# 1.net
KiCad netlist of a schematic drawn in EAGLE
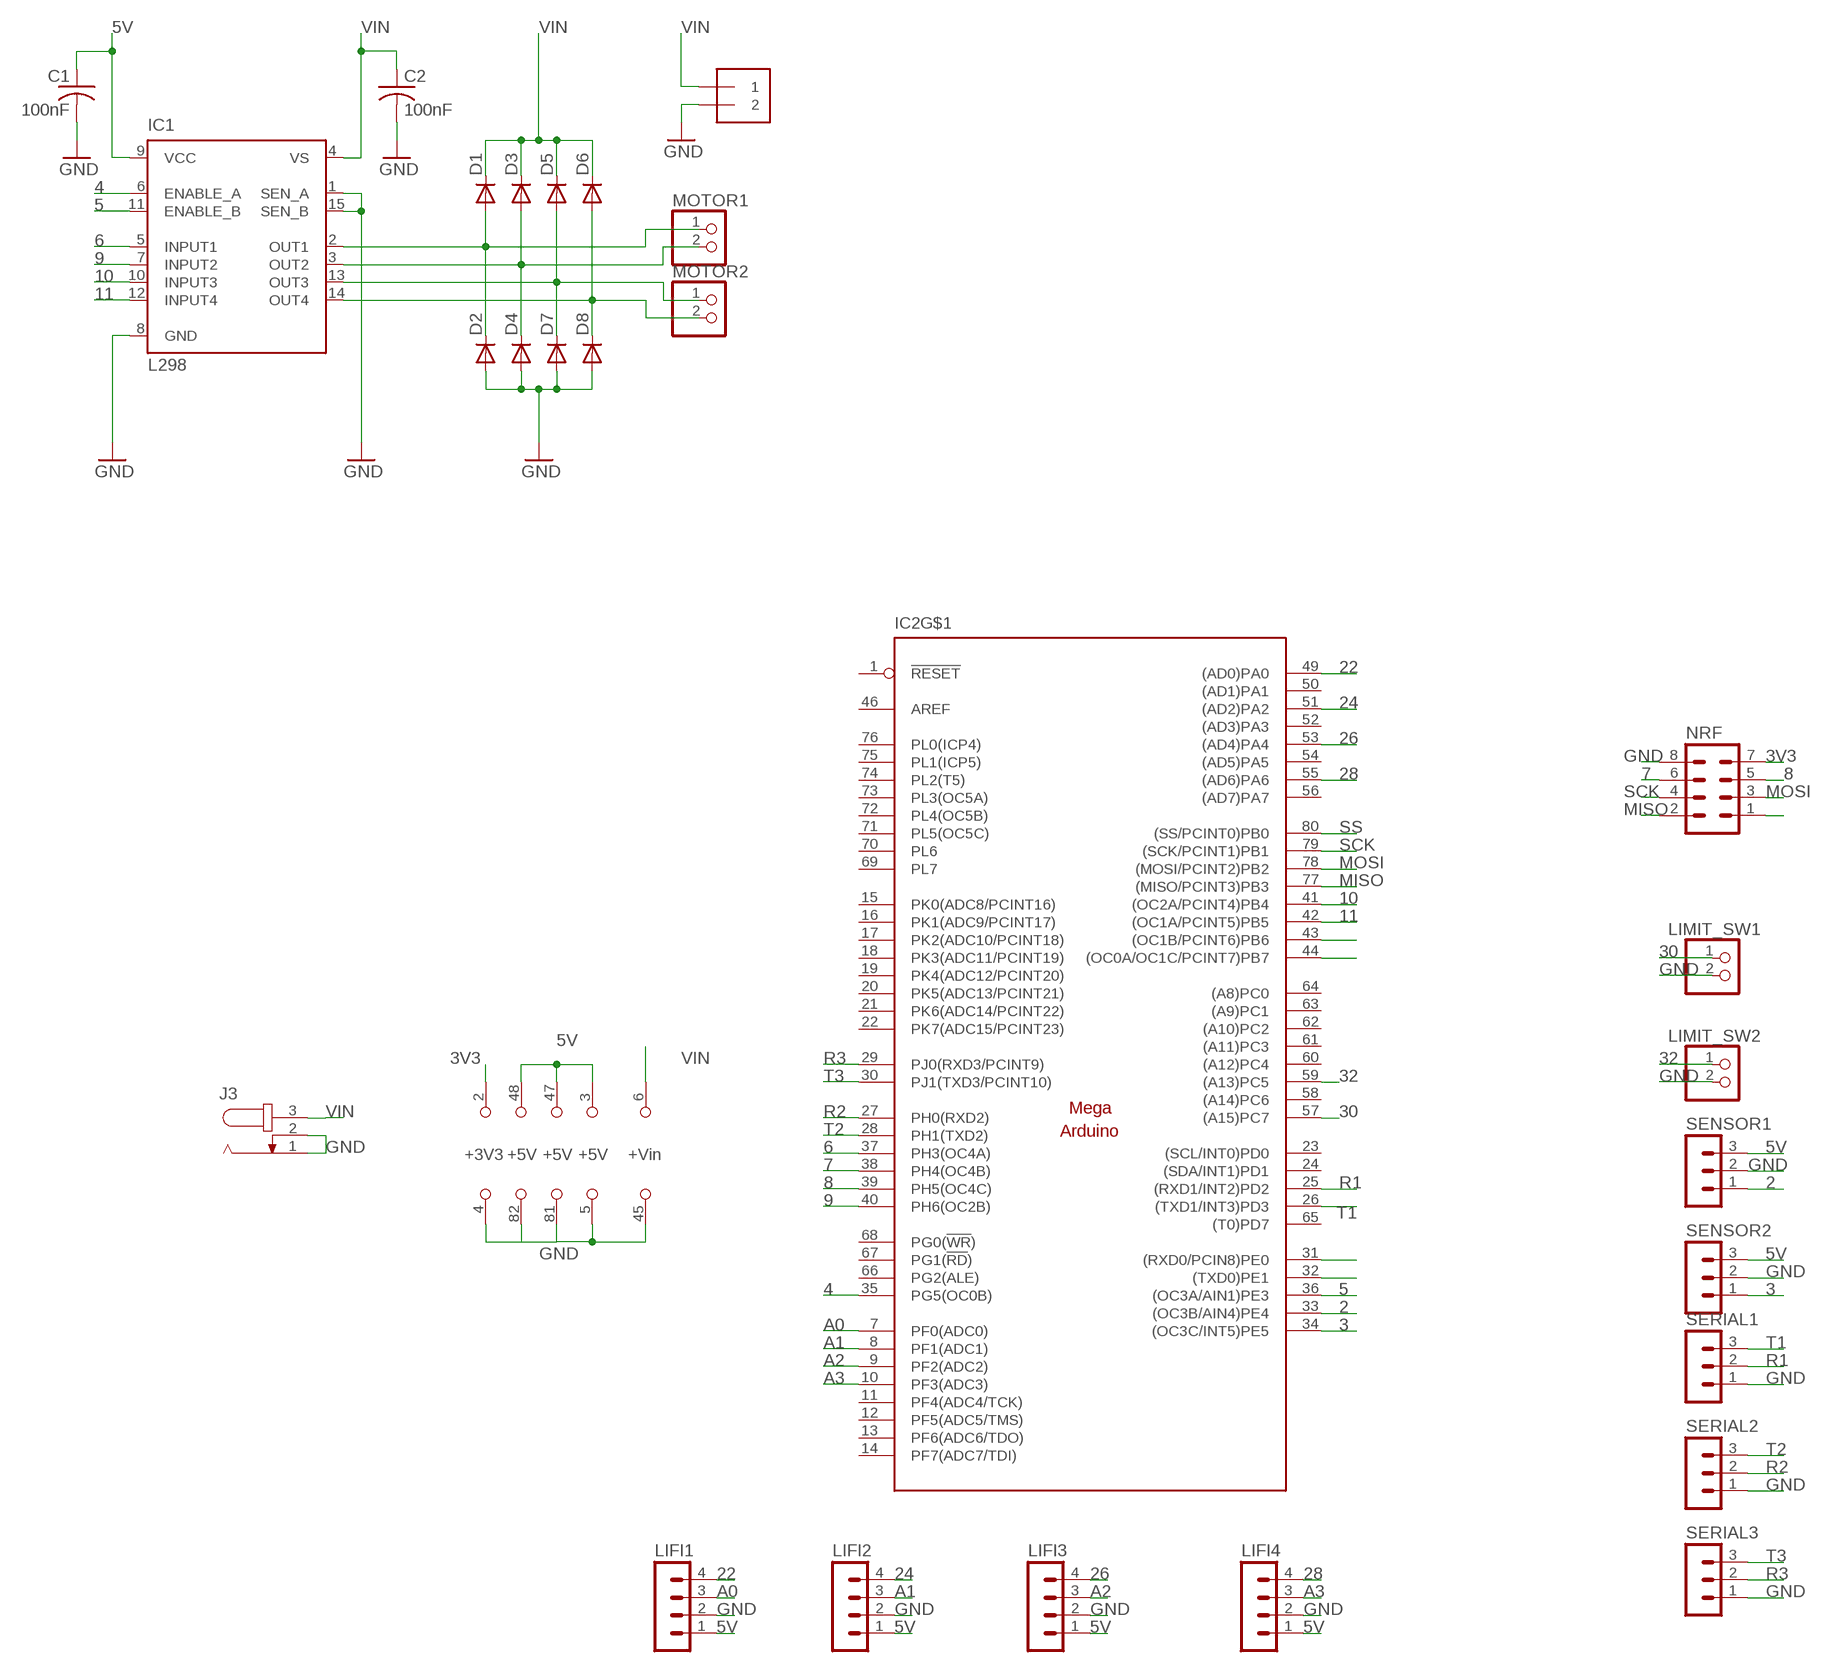
[diagram p0: schematic, sheet 1]

(export (version "E")
  (design (tool "Eeschema 10.0.6"))
  (components
    (comp (ref "C1")
      (value "100nF")
      (footprint "eagle-import:C050-024X044")
      (libsource (lib "eagle-import") (part "C-US050-024X044"))
    )
    (comp (ref "C2")
      (value "100nF")
      (footprint "eagle-import:C050-024X044")
      (libsource (lib "eagle-import") (part "C-US050-024X044"))
    )
    (comp (ref "D1")
      (value "DIODE-D-5")
      (footprint "eagle-import:D-5")
      (libsource (lib "eagle-import") (part "DIODE-D-5"))
    )
    (comp (ref "D2")
      (value "DIODE-D-5")
      (footprint "eagle-import:D-5")
      (libsource (lib "eagle-import") (part "DIODE-D-5"))
    )
    (comp (ref "D3")
      (value "DIODE-D-5")
      (footprint "eagle-import:D-5")
      (libsource (lib "eagle-import") (part "DIODE-D-5"))
    )
    (comp (ref "D4")
      (value "DIODE-D-5")
      (footprint "eagle-import:D-5")
      (libsource (lib "eagle-import") (part "DIODE-D-5"))
    )
    (comp (ref "D5")
      (value "DIODE-D-5")
      (footprint "eagle-import:D-5")
      (libsource (lib "eagle-import") (part "DIODE-D-5"))
    )
    (comp (ref "D6")
      (value "DIODE-D-5")
      (footprint "eagle-import:D-5")
      (libsource (lib "eagle-import") (part "DIODE-D-5"))
    )
    (comp (ref "D7")
      (value "DIODE-D-5")
      (footprint "eagle-import:D-5")
      (libsource (lib "eagle-import") (part "DIODE-D-5"))
    )
    (comp (ref "D8")
      (value "DIODE-D-5")
      (footprint "eagle-import:D-5")
      (libsource (lib "eagle-import") (part "DIODE-D-5"))
    )
    (comp (ref "IC1")
      (value "L298")
      (footprint "eagle-import:MULTIWATT-15")
      (fields (field (name "MPN") "L298N"))
      (libsource (lib "eagle-import") (part "L298"))
    )
    (comp (ref "IC2")
      (value "MEGAARDUINO_21")
      (footprint "eagle-import:MEGA_ARDUINO_1")
      (libsource (lib "eagle-import") (part "MEGAARDUINO_21"))
    )
    (comp (ref "J1")
      (value "1X2-3.5MM")
      (footprint "eagle-import:1X2-3.5MM")
      (libsource (lib "eagle-import") (part "1X2-3.5MM"))
    )
    (comp (ref "J3")
      (value "JACK-PLUG0")
      (footprint "eagle-import:SPC4077")
      (libsource (lib "eagle-import") (part "JACK-PLUG0"))
    )
    (comp (ref "LIFI1")
      (value "MA04-1")
      (footprint "eagle-import:MA04-1")
      (libsource (lib "eagle-import") (part "MA04-1"))
    )
    (comp (ref "LIFI2")
      (value "MA04-1")
      (footprint "eagle-import:MA04-1")
      (libsource (lib "eagle-import") (part "MA04-1"))
    )
    (comp (ref "LIFI3")
      (value "MA04-1")
      (footprint "eagle-import:MA04-1")
      (libsource (lib "eagle-import") (part "MA04-1"))
    )
    (comp (ref "LIFI4")
      (value "MA04-1")
      (footprint "eagle-import:MA04-1")
      (libsource (lib "eagle-import") (part "MA04-1"))
    )
    (comp (ref "LIMIT_SW1")
      (value "PINHD-1X2")
      (footprint "eagle-import:1X02")
      (libsource (lib "eagle-import") (part "PINHD-1X2"))
    )
    (comp (ref "LIMIT_SW2")
      (value "PINHD-1X2")
      (footprint "eagle-import:1X02")
      (libsource (lib "eagle-import") (part "PINHD-1X2"))
    )
    (comp (ref "MOTOR1")
      (value "PINHD-1X2")
      (footprint "eagle-import:1X02")
      (libsource (lib "eagle-import") (part "PINHD-1X2"))
    )
    (comp (ref "MOTOR2")
      (value "PINHD-1X2")
      (footprint "eagle-import:1X02")
      (libsource (lib "eagle-import") (part "PINHD-1X2"))
    )
    (comp (ref "NRF")
      (value "MA04-2")
      (footprint "eagle-import:MA04-2")
      (libsource (lib "eagle-import") (part "MA04-2"))
    )
    (comp (ref "SENSOR1")
      (value "MA03-1")
      (footprint "eagle-import:MA03-1")
      (libsource (lib "eagle-import") (part "MA03-1"))
    )
    (comp (ref "SENSOR2")
      (value "MA03-1")
      (footprint "eagle-import:MA03-1")
      (libsource (lib "eagle-import") (part "MA03-1"))
    )
    (comp (ref "SERIAL1")
      (value "MA03-1")
      (footprint "eagle-import:MA03-1")
      (libsource (lib "eagle-import") (part "MA03-1"))
    )
    (comp (ref "SERIAL2")
      (value "MA03-1")
      (footprint "eagle-import:MA03-1")
      (libsource (lib "eagle-import") (part "MA03-1"))
    )
    (comp (ref "SERIAL3")
      (value "MA03-1")
      (footprint "eagle-import:MA03-1")
      (libsource (lib "eagle-import") (part "MA03-1"))
    )
  )
  (nets
    (net (code "1") (name "/2") (class "Default")
      (node (ref "IC2") (pin "33") (pinfunction "(OC3B/AIN4)PE4_33") (pintype "bidirectional"))
      (node (ref "SENSOR1") (pin "1") (pinfunction "1_1") (pintype "passive"))
    )
    (net (code "2") (name "/3") (class "Default")
      (node (ref "IC2") (pin "34") (pinfunction "(OC3C/INT5)PE5_34") (pintype "bidirectional"))
      (node (ref "SENSOR2") (pin "1") (pinfunction "1_1") (pintype "passive"))
    )
    (net (code "3") (name "/3V3") (class "Default")
      (node (ref "IC2") (pin "2") (pinfunction "+3V3_2") (pintype "power_in"))
      (node (ref "NRF") (pin "7") (pinfunction "7_7") (pintype "passive"))
    )
    (net (code "4") (name "/4") (class "Default")
      (node (ref "IC1") (pin "6") (pinfunction "ENABLE_A_6") (pintype "input"))
      (node (ref "IC2") (pin "35") (pinfunction "PG5(OC0B)_35") (pintype "bidirectional"))
    )
    (net (code "5") (name "/5") (class "Default")
      (node (ref "IC1") (pin "11") (pinfunction "ENABLE_B_11") (pintype "input"))
      (node (ref "IC2") (pin "36") (pinfunction "(OC3A/AIN1)PE3_36") (pintype "bidirectional"))
    )
    (net (code "6") (name "/5V") (class "Default")
      (node (ref "C1") (pin "1") (pinfunction "1_1") (pintype "passive"))
      (node (ref "IC1") (pin "9") (pinfunction "VCC_9") (pintype "power_in"))
      (node (ref "IC2") (pin "3") (pinfunction "+5V_3") (pintype "power_in"))
      (node (ref "IC2") (pin "47") (pinfunction "+5V_47") (pintype "power_in"))
      (node (ref "IC2") (pin "48") (pinfunction "+5V_48") (pintype "power_in"))
      (node (ref "LIFI1") (pin "1") (pinfunction "1_1") (pintype "passive"))
      (node (ref "LIFI2") (pin "1") (pinfunction "1_1") (pintype "passive"))
      (node (ref "LIFI3") (pin "1") (pinfunction "1_1") (pintype "passive"))
      (node (ref "LIFI4") (pin "1") (pinfunction "1_1") (pintype "passive"))
      (node (ref "SENSOR1") (pin "3") (pinfunction "3_3") (pintype "passive"))
      (node (ref "SENSOR2") (pin "3") (pinfunction "3_3") (pintype "passive"))
    )
    (net (code "7") (name "/6") (class "Default")
      (node (ref "IC1") (pin "5") (pinfunction "INPUT1_5") (pintype "input"))
      (node (ref "IC2") (pin "37") (pinfunction "PH3(OC4A)_37") (pintype "bidirectional"))
    )
    (net (code "8") (name "/7") (class "Default")
      (node (ref "IC2") (pin "38") (pinfunction "PH4(OC4B)_38") (pintype "bidirectional"))
      (node (ref "NRF") (pin "6") (pinfunction "6_6") (pintype "passive"))
    )
    (net (code "9") (name "/8") (class "Default")
      (node (ref "IC2") (pin "39") (pinfunction "PH5(OC4C)_39") (pintype "bidirectional"))
      (node (ref "NRF") (pin "5") (pinfunction "5_5") (pintype "passive"))
    )
    (net (code "10") (name "/9") (class "Default")
      (node (ref "IC1") (pin "7") (pinfunction "INPUT2_7") (pintype "input"))
      (node (ref "IC2") (pin "40") (pinfunction "PH6(OC2B)_40") (pintype "bidirectional"))
    )
    (net (code "11") (name "/10") (class "Default")
      (node (ref "IC1") (pin "10") (pinfunction "INPUT3_10") (pintype "input"))
      (node (ref "IC2") (pin "41") (pinfunction "(OC2A/PCINT4)PB4_41") (pintype "bidirectional"))
    )
    (net (code "12") (name "/11") (class "Default")
      (node (ref "IC1") (pin "12") (pinfunction "INPUT4_12") (pintype "input"))
      (node (ref "IC2") (pin "42") (pinfunction "(OC1A/PCINT5)PB5_42") (pintype "bidirectional"))
    )
    (net (code "13") (name "/22") (class "Default")
      (node (ref "IC2") (pin "49") (pinfunction "(AD0)PA0_49") (pintype "bidirectional"))
      (node (ref "LIFI1") (pin "4") (pinfunction "4_4") (pintype "passive"))
    )
    (net (code "14") (name "/24") (class "Default")
      (node (ref "IC2") (pin "51") (pinfunction "(AD2)PA2_51") (pintype "bidirectional"))
      (node (ref "LIFI2") (pin "4") (pinfunction "4_4") (pintype "passive"))
    )
    (net (code "15") (name "/26") (class "Default")
      (node (ref "IC2") (pin "53") (pinfunction "(AD4)PA4_53") (pintype "bidirectional"))
      (node (ref "LIFI3") (pin "4") (pinfunction "4_4") (pintype "passive"))
    )
    (net (code "16") (name "/28") (class "Default")
      (node (ref "IC2") (pin "55") (pinfunction "(AD6)PA6_55") (pintype "bidirectional"))
      (node (ref "LIFI4") (pin "4") (pinfunction "4_4") (pintype "passive"))
    )
    (net (code "17") (name "/30") (class "Default")
      (node (ref "IC2") (pin "57") (pinfunction "(A15)PC7_57") (pintype "bidirectional"))
      (node (ref "LIMIT_SW1") (pin "1") (pinfunction "1_1") (pintype "passive"))
    )
    (net (code "18") (name "/32") (class "Default")
      (node (ref "IC2") (pin "59") (pinfunction "(A13)PC5_59") (pintype "bidirectional"))
      (node (ref "LIMIT_SW2") (pin "1") (pinfunction "1_1") (pintype "passive"))
    )
    (net (code "19") (name "/A0") (class "Default")
      (node (ref "IC2") (pin "7") (pinfunction "PF0(ADC0)_7") (pintype "bidirectional"))
      (node (ref "LIFI1") (pin "3") (pinfunction "3_3") (pintype "passive"))
    )
    (net (code "20") (name "/A1") (class "Default")
      (node (ref "IC2") (pin "8") (pinfunction "PF1(ADC1)_8") (pintype "bidirectional"))
      (node (ref "LIFI2") (pin "3") (pinfunction "3_3") (pintype "passive"))
    )
    (net (code "21") (name "/A2") (class "Default")
      (node (ref "IC2") (pin "9") (pinfunction "PF2(ADC2)_9") (pintype "bidirectional"))
      (node (ref "LIFI3") (pin "3") (pinfunction "3_3") (pintype "passive"))
    )
    (net (code "22") (name "/A3") (class "Default")
      (node (ref "IC2") (pin "10") (pinfunction "PF3(ADC3)_10") (pintype "bidirectional"))
      (node (ref "LIFI4") (pin "3") (pinfunction "3_3") (pintype "passive"))
    )
    (net (code "23") (name "/MISO") (class "Default")
      (node (ref "IC2") (pin "77") (pinfunction "(MISO/PCINT3)PB3_77") (pintype "bidirectional"))
      (node (ref "NRF") (pin "2") (pinfunction "2_2") (pintype "passive"))
    )
    (net (code "24") (name "/MOSI") (class "Default")
      (node (ref "IC2") (pin "78") (pinfunction "(MOSI/PCINT2)PB2_78") (pintype "bidirectional"))
      (node (ref "NRF") (pin "3") (pinfunction "3_3") (pintype "passive"))
    )
    (net (code "25") (name "/R1") (class "Default")
      (node (ref "IC2") (pin "25") (pinfunction "(RXD1/INT2)PD2_25") (pintype "bidirectional"))
      (node (ref "SERIAL1") (pin "2") (pinfunction "2_2") (pintype "passive"))
    )
    (net (code "26") (name "/R2") (class "Default")
      (node (ref "IC2") (pin "27") (pinfunction "PH0(RXD2)_27") (pintype "bidirectional"))
      (node (ref "SERIAL2") (pin "2") (pinfunction "2_2") (pintype "passive"))
    )
    (net (code "27") (name "/R3") (class "Default")
      (node (ref "IC2") (pin "29") (pinfunction "PJ0(RXD3/PCINT9)_29") (pintype "bidirectional"))
      (node (ref "SERIAL3") (pin "2") (pinfunction "2_2") (pintype "passive"))
    )
    (net (code "28") (name "/SCK") (class "Default")
      (node (ref "IC2") (pin "79") (pinfunction "(SCK/PCINT1)PB1_79") (pintype "bidirectional"))
      (node (ref "NRF") (pin "4") (pinfunction "4_4") (pintype "passive"))
    )
    (net (code "29") (name "/SS") (class "Default")
      (node (ref "IC2") (pin "80") (pinfunction "(SS/PCINT0)PB0_80") (pintype "bidirectional"))
    )
    (net (code "30") (name "/T1") (class "Default")
      (node (ref "IC2") (pin "26") (pinfunction "(TXD1/INT3)PD3_26") (pintype "bidirectional"))
      (node (ref "SERIAL1") (pin "3") (pinfunction "3_3") (pintype "passive"))
    )
    (net (code "31") (name "/T2") (class "Default")
      (node (ref "IC2") (pin "28") (pinfunction "PH1(TXD2)_28") (pintype "bidirectional"))
      (node (ref "SERIAL2") (pin "3") (pinfunction "3_3") (pintype "passive"))
    )
    (net (code "32") (name "/T3") (class "Default")
      (node (ref "IC2") (pin "30") (pinfunction "PJ1(TXD3/PCINT10)_30") (pintype "bidirectional"))
      (node (ref "SERIAL3") (pin "3") (pinfunction "3_3") (pintype "passive"))
    )
    (net (code "33") (name "/VIN") (class "Default")
      (node (ref "C2") (pin "1") (pinfunction "1_1") (pintype "passive"))
      (node (ref "D1") (pin "C") (pinfunction "C_C") (pintype "passive"))
      (node (ref "D3") (pin "C") (pinfunction "C_C") (pintype "passive"))
      (node (ref "D5") (pin "C") (pinfunction "C_C") (pintype "passive"))
      (node (ref "D6") (pin "C") (pinfunction "C_C") (pintype "passive"))
      (node (ref "IC1") (pin "4") (pinfunction "VS_4") (pintype "power_in"))
      (node (ref "IC2") (pin "6") (pinfunction "+VIN_6") (pintype "power_in"))
      (node (ref "J1") (pin "1") (pinfunction "1_1") (pintype "passive"))
      (node (ref "J3") (pin "3") (pinfunction "3_3") (pintype "passive"))
    )
    (net (code "34") (name "GND") (class "Default")
      (node (ref "C1") (pin "2") (pinfunction "2_2") (pintype "passive"))
      (node (ref "C2") (pin "2") (pinfunction "2_2") (pintype "passive"))
      (node (ref "D2") (pin "A") (pinfunction "A_A") (pintype "passive"))
      (node (ref "D4") (pin "A") (pinfunction "A_A") (pintype "passive"))
      (node (ref "D7") (pin "A") (pinfunction "A_A") (pintype "passive"))
      (node (ref "D8") (pin "A") (pinfunction "A_A") (pintype "passive"))
      (node (ref "IC1") (pin "1") (pinfunction "SEN_A_1") (pintype "input"))
      (node (ref "IC1") (pin "15") (pinfunction "SEN_B_15") (pintype "input"))
      (node (ref "IC1") (pin "8") (pinfunction "GND_8") (pintype "power_in"))
      (node (ref "IC2") (pin "4") (pinfunction "GND_4") (pintype "power_in"))
      (node (ref "IC2") (pin "45") (pinfunction "GND_45") (pintype "power_in"))
      (node (ref "IC2") (pin "5") (pinfunction "GND_5") (pintype "power_in"))
      (node (ref "IC2") (pin "81") (pinfunction "GND_81") (pintype "power_in"))
      (node (ref "IC2") (pin "82") (pinfunction "GND_82") (pintype "power_in"))
      (node (ref "J1") (pin "2") (pinfunction "2_2") (pintype "passive"))
      (node (ref "J3") (pin "1") (pinfunction "1_1") (pintype "passive"))
      (node (ref "J3") (pin "2") (pinfunction "2_2") (pintype "passive"))
      (node (ref "LIFI1") (pin "2") (pinfunction "2_2") (pintype "passive"))
      (node (ref "LIFI2") (pin "2") (pinfunction "2_2") (pintype "passive"))
      (node (ref "LIFI3") (pin "2") (pinfunction "2_2") (pintype "passive"))
      (node (ref "LIFI4") (pin "2") (pinfunction "2_2") (pintype "passive"))
      (node (ref "LIMIT_SW1") (pin "2") (pinfunction "2_2") (pintype "passive"))
      (node (ref "LIMIT_SW2") (pin "2") (pinfunction "2_2") (pintype "passive"))
      (node (ref "NRF") (pin "8") (pinfunction "8_8") (pintype "passive"))
      (node (ref "SENSOR1") (pin "2") (pinfunction "2_2") (pintype "passive"))
      (node (ref "SENSOR2") (pin "2") (pinfunction "2_2") (pintype "passive"))
      (node (ref "SERIAL1") (pin "1") (pinfunction "1_1") (pintype "passive"))
      (node (ref "SERIAL2") (pin "1") (pinfunction "1_1") (pintype "passive"))
      (node (ref "SERIAL3") (pin "1") (pinfunction "1_1") (pintype "passive"))
    )
    (net (code "35") (name "Net-(IC1-OUT1)") (class "Default")
      (node (ref "D1") (pin "A") (pinfunction "A_A") (pintype "passive"))
      (node (ref "D2") (pin "C") (pinfunction "C_C") (pintype "passive"))
      (node (ref "IC1") (pin "2") (pinfunction "OUT1_2") (pintype "output"))
      (node (ref "MOTOR1") (pin "1") (pinfunction "1_1") (pintype "passive"))
    )
    (net (code "36") (name "Net-(IC1-OUT2)") (class "Default")
      (node (ref "D3") (pin "A") (pinfunction "A_A") (pintype "passive"))
      (node (ref "D4") (pin "C") (pinfunction "C_C") (pintype "passive"))
      (node (ref "IC1") (pin "3") (pinfunction "OUT2_3") (pintype "output"))
      (node (ref "MOTOR1") (pin "2") (pinfunction "2_2") (pintype "passive"))
    )
    (net (code "37") (name "Net-(IC1-OUT3)") (class "Default")
      (node (ref "D5") (pin "A") (pinfunction "A_A") (pintype "passive"))
      (node (ref "D7") (pin "C") (pinfunction "C_C") (pintype "passive"))
      (node (ref "IC1") (pin "13") (pinfunction "OUT3_13") (pintype "output"))
      (node (ref "MOTOR2") (pin "1") (pinfunction "1_1") (pintype "passive"))
    )
    (net (code "38") (name "Net-(IC1-OUT4)") (class "Default")
      (node (ref "D6") (pin "A") (pinfunction "A_A") (pintype "passive"))
      (node (ref "D8") (pin "C") (pinfunction "C_C") (pintype "passive"))
      (node (ref "IC1") (pin "14") (pinfunction "OUT4_14") (pintype "output"))
      (node (ref "MOTOR2") (pin "2") (pinfunction "2_2") (pintype "passive"))
    )
    (net (code "39") (name "unconnected-(IC2A-(A8)PC0-Pad64)") (class "Default")
      (node (ref "IC2") (pin "64") (pinfunction "(A8)PC0_64") (pintype "bidirectional"))
    )
    (net (code "40") (name "unconnected-(IC2A-(A9)PC1-Pad63)") (class "Default")
      (node (ref "IC2") (pin "63") (pinfunction "(A9)PC1_63") (pintype "bidirectional"))
    )
    (net (code "41") (name "unconnected-(IC2A-(A10)PC2-Pad62)") (class "Default")
      (node (ref "IC2") (pin "62") (pinfunction "(A10)PC2_62") (pintype "bidirectional"))
    )
    (net (code "42") (name "unconnected-(IC2A-(A11)PC3-Pad61)") (class "Default")
      (node (ref "IC2") (pin "61") (pinfunction "(A11)PC3_61") (pintype "bidirectional"))
    )
    (net (code "43") (name "unconnected-(IC2A-(A12)PC4-Pad60)") (class "Default")
      (node (ref "IC2") (pin "60") (pinfunction "(A12)PC4_60") (pintype "bidirectional"))
    )
    (net (code "44") (name "unconnected-(IC2A-(A14)PC6-Pad58)") (class "Default")
      (node (ref "IC2") (pin "58") (pinfunction "(A14)PC6_58") (pintype "bidirectional"))
    )
    (net (code "45") (name "unconnected-(IC2A-(AD1)PA1-Pad50)") (class "Default")
      (node (ref "IC2") (pin "50") (pinfunction "(AD1)PA1_50") (pintype "bidirectional"))
    )
    (net (code "46") (name "unconnected-(IC2A-(AD3)PA3-Pad52)") (class "Default")
      (node (ref "IC2") (pin "52") (pinfunction "(AD3)PA3_52") (pintype "bidirectional"))
    )
    (net (code "47") (name "unconnected-(IC2A-(AD5)PA5-Pad54)") (class "Default")
      (node (ref "IC2") (pin "54") (pinfunction "(AD5)PA5_54") (pintype "bidirectional"))
    )
    (net (code "48") (name "unconnected-(IC2A-(AD7)PA7-Pad56)") (class "Default")
      (node (ref "IC2") (pin "56") (pinfunction "(AD7)PA7_56") (pintype "bidirectional"))
    )
    (net (code "49") (name "unconnected-(IC2A-(OC0A{slash}OC1C{slash}PCINT7)PB7-Pad44)") (class "Default")
      (node (ref "IC2") (pin "44") (pinfunction "(OC0A/OC1C/PCINT7)PB7_44") (pintype "bidirectional"))
    )
    (net (code "50") (name "unconnected-(IC2A-(OC1B{slash}PCINT6)PB6-Pad43)") (class "Default")
      (node (ref "IC2") (pin "43") (pinfunction "(OC1B/PCINT6)PB6_43") (pintype "bidirectional"))
    )
    (net (code "51") (name "unconnected-(IC2A-(RXD0{slash}PCIN8)PE0-Pad31)") (class "Default")
      (node (ref "IC2") (pin "31") (pinfunction "(RXD0/PCIN8)PE0_31") (pintype "bidirectional"))
    )
    (net (code "52") (name "unconnected-(IC2A-(SCL{slash}INT0)PD0-Pad23)") (class "Default")
      (node (ref "IC2") (pin "23") (pinfunction "(SCL/INT0)PD0_23") (pintype "bidirectional"))
    )
    (net (code "53") (name "unconnected-(IC2A-(SDA{slash}INT1)PD1-Pad24)") (class "Default")
      (node (ref "IC2") (pin "24") (pinfunction "(SDA/INT1)PD1_24") (pintype "bidirectional"))
    )
    (net (code "54") (name "unconnected-(IC2A-(T0)PD7-Pad65)") (class "Default")
      (node (ref "IC2") (pin "65") (pinfunction "(T0)PD7_65") (pintype "bidirectional"))
    )
    (net (code "55") (name "unconnected-(IC2A-(TXD0)PE1-Pad32)") (class "Default")
      (node (ref "IC2") (pin "32") (pinfunction "(TXD0)PE1_32") (pintype "bidirectional"))
    )
    (net (code "56") (name "unconnected-(IC2A-AREF-Pad46)") (class "Default")
      (node (ref "IC2") (pin "46") (pinfunction "AREF_46") (pintype "bidirectional"))
    )
    (net (code "57") (name "unconnected-(IC2A-PF4(ADC4{slash}TCK)-Pad11)") (class "Default")
      (node (ref "IC2") (pin "11") (pinfunction "PF4(ADC4/TCK)_11") (pintype "bidirectional"))
    )
    (net (code "58") (name "unconnected-(IC2A-PF5(ADC5{slash}TMS)-Pad12)") (class "Default")
      (node (ref "IC2") (pin "12") (pinfunction "PF5(ADC5/TMS)_12") (pintype "bidirectional"))
    )
    (net (code "59") (name "unconnected-(IC2A-PF6(ADC6{slash}TDO)-Pad13)") (class "Default")
      (node (ref "IC2") (pin "13") (pinfunction "PF6(ADC6/TDO)_13") (pintype "bidirectional"))
    )
    (net (code "60") (name "unconnected-(IC2A-PF7(ADC7{slash}TDI)-Pad14)") (class "Default")
      (node (ref "IC2") (pin "14") (pinfunction "PF7(ADC7/TDI)_14") (pintype "bidirectional"))
    )
    (net (code "61") (name "unconnected-(IC2A-PG0(~{WR})-Pad68)") (class "Default")
      (node (ref "IC2") (pin "68") (pinfunction "PG0(~{WR})_68") (pintype "bidirectional"))
    )
    (net (code "62") (name "unconnected-(IC2A-PG1(~{RD})-Pad67)") (class "Default")
      (node (ref "IC2") (pin "67") (pinfunction "PG1(~{RD})_67") (pintype "bidirectional"))
    )
    (net (code "63") (name "unconnected-(IC2A-PG2(ALE)-Pad66)") (class "Default")
      (node (ref "IC2") (pin "66") (pinfunction "PG2(ALE)_66") (pintype "bidirectional"))
    )
    (net (code "64") (name "unconnected-(IC2A-PK0(ADC8{slash}PCINT16)-Pad15)") (class "Default")
      (node (ref "IC2") (pin "15") (pinfunction "PK0(ADC8/PCINT16)_15") (pintype "bidirectional"))
    )
    (net (code "65") (name "unconnected-(IC2A-PK1(ADC9{slash}PCINT17)-Pad16)") (class "Default")
      (node (ref "IC2") (pin "16") (pinfunction "PK1(ADC9/PCINT17)_16") (pintype "bidirectional"))
    )
    (net (code "66") (name "unconnected-(IC2A-PK2(ADC10{slash}PCINT18)-Pad17)") (class "Default")
      (node (ref "IC2") (pin "17") (pinfunction "PK2(ADC10/PCINT18)_17") (pintype "bidirectional"))
    )
    (net (code "67") (name "unconnected-(IC2A-PK3(ADC11{slash}PCINT19)-Pad18)") (class "Default")
      (node (ref "IC2") (pin "18") (pinfunction "PK3(ADC11/PCINT19)_18") (pintype "bidirectional"))
    )
    (net (code "68") (name "unconnected-(IC2A-PK4(ADC12{slash}PCINT20)-Pad19)") (class "Default")
      (node (ref "IC2") (pin "19") (pinfunction "PK4(ADC12/PCINT20)_19") (pintype "bidirectional"))
    )
    (net (code "69") (name "unconnected-(IC2A-PK5(ADC13{slash}PCINT21)-Pad20)") (class "Default")
      (node (ref "IC2") (pin "20") (pinfunction "PK5(ADC13/PCINT21)_20") (pintype "bidirectional"))
    )
    (net (code "70") (name "unconnected-(IC2A-PK6(ADC14{slash}PCINT22)-Pad21)") (class "Default")
      (node (ref "IC2") (pin "21") (pinfunction "PK6(ADC14/PCINT22)_21") (pintype "bidirectional"))
    )
    (net (code "71") (name "unconnected-(IC2A-PK7(ADC15{slash}PCINT23)-Pad22)") (class "Default")
      (node (ref "IC2") (pin "22") (pinfunction "PK7(ADC15/PCINT23)_22") (pintype "bidirectional"))
    )
    (net (code "72") (name "unconnected-(IC2A-PL0(ICP4)-Pad76)") (class "Default")
      (node (ref "IC2") (pin "76") (pinfunction "PL0(ICP4)_76") (pintype "bidirectional"))
    )
    (net (code "73") (name "unconnected-(IC2A-PL1(ICP5)-Pad75)") (class "Default")
      (node (ref "IC2") (pin "75") (pinfunction "PL1(ICP5)_75") (pintype "bidirectional"))
    )
    (net (code "74") (name "unconnected-(IC2A-PL2(T5)-Pad74)") (class "Default")
      (node (ref "IC2") (pin "74") (pinfunction "PL2(T5)_74") (pintype "bidirectional"))
    )
    (net (code "75") (name "unconnected-(IC2A-PL3(OC5A)-Pad73)") (class "Default")
      (node (ref "IC2") (pin "73") (pinfunction "PL3(OC5A)_73") (pintype "bidirectional"))
    )
    (net (code "76") (name "unconnected-(IC2A-PL4(OC5B)-Pad72)") (class "Default")
      (node (ref "IC2") (pin "72") (pinfunction "PL4(OC5B)_72") (pintype "bidirectional"))
    )
    (net (code "77") (name "unconnected-(IC2A-PL5(OC5C)-Pad71)") (class "Default")
      (node (ref "IC2") (pin "71") (pinfunction "PL5(OC5C)_71") (pintype "bidirectional"))
    )
    (net (code "78") (name "unconnected-(IC2A-PL6-Pad70)") (class "Default")
      (node (ref "IC2") (pin "70") (pinfunction "PL6_70") (pintype "bidirectional"))
    )
    (net (code "79") (name "unconnected-(IC2A-PL7-Pad69)") (class "Default")
      (node (ref "IC2") (pin "69") (pinfunction "PL7_69") (pintype "bidirectional"))
    )
    (net (code "80") (name "unconnected-(IC2A-~{RESET}-Pad1)") (class "Default")
      (node (ref "IC2") (pin "1") (pinfunction "~{RESET}_1") (pintype "bidirectional"))
    )
    (net (code "81") (name "unconnected-(NRF-Pad1)") (class "Default")
      (node (ref "NRF") (pin "1") (pinfunction "1_1") (pintype "passive"))
    )
  )
)
